# amplivias.net
KiCad netlist of a schematic drawn in EAGLE
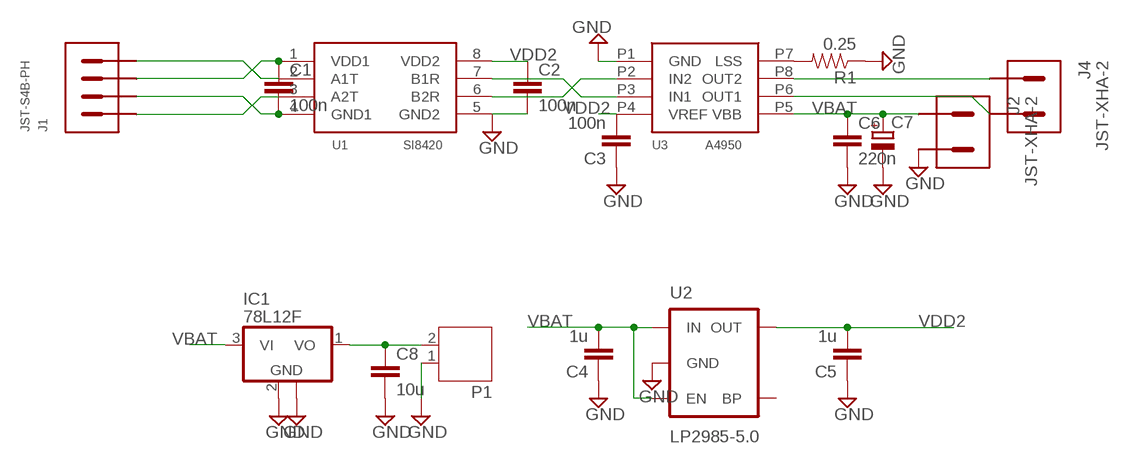
[diagram p0: schematic, sheet 1]

(export (version "E")
  (design (tool "Eeschema 10.0.6"))
  (components
    (comp (ref "C1")
      (value "100n")
      (footprint "eagle-import:0603-CAP")
      (libsource (lib "eagle-import") (part "CAP0603-CAP"))
    )
    (comp (ref "C2")
      (value "100n")
      (footprint "eagle-import:0603-CAP")
      (libsource (lib "eagle-import") (part "CAP0603-CAP"))
    )
    (comp (ref "C3")
      (value "100n")
      (footprint "eagle-import:0603-CAP")
      (libsource (lib "eagle-import") (part "CAP0603-CAP"))
    )
    (comp (ref "C4")
      (value "1u")
      (footprint "eagle-import:0603-CAP")
      (libsource (lib "eagle-import") (part "CAP0603-CAP"))
    )
    (comp (ref "C5")
      (value "1u")
      (footprint "eagle-import:0603-CAP")
      (libsource (lib "eagle-import") (part "CAP0603-CAP"))
    )
    (comp (ref "C6")
      (value "220n")
      (footprint "eagle-import:C0805")
      (libsource (lib "eagle-import") (part "C-EUC0805"))
    )
    (comp (ref "C7")
      (value "CPOL-EUSANYO_SMD_E7")
      (footprint "eagle-import:SANYO-OSCON_SMD_E7")
      (libsource (lib "eagle-import") (part "CPOL-EUSANYO_SMD_E7"))
    )
    (comp (ref "C8")
      (value "10u")
      (footprint "eagle-import:C0805")
      (libsource (lib "eagle-import") (part "C-EUC0805"))
    )
    (comp (ref "IC1")
      (value "78L12F")
      (footprint "eagle-import:SOT89")
      (libsource (lib "eagle-import") (part "78LF12"))
    )
    (comp (ref "J1")
      (value "JST-S4B-PH")
      (footprint "eagle-import:JST-S4B-PH")
      (libsource (lib "eagle-import") (part "JST-S4B-PH"))
    )
    (comp (ref "J2")
      (value "JST-XHA-2")
      (footprint "eagle-import:JST-XHA-2")
      (libsource (lib "eagle-import") (part "JST-XHA-2"))
    )
    (comp (ref "J4")
      (value "JST-XHA-2")
      (footprint "eagle-import:JST-XHA-2")
      (libsource (lib "eagle-import") (part "JST-XHA-2"))
    )
    (comp (ref "P1")
      (value "JST-PH2")
      (footprint "eagle-import:JST-PH2")
      (libsource (lib "eagle-import") (part "JST-PH2"))
    )
    (comp (ref "R1")
      (value "0.25")
      (footprint "eagle-import:R2512")
      (libsource (lib "eagle-import") (part "RESISTOR2512"))
    )
    (comp (ref "U1")
      (value "SI8420")
      (footprint "eagle-import:SO-08")
      (libsource (lib "eagle-import") (part "SI8420"))
    )
    (comp (ref "U2")
      (value "LP2985-5.0")
      (footprint "eagle-import:SOT23-5")
      (libsource (lib "eagle-import") (part "MIC52055V"))
    )
    (comp (ref "U3")
      (value "A4950")
      (footprint "eagle-import:SOIC8THROUG")
      (libsource (lib "eagle-import") (part "A4950"))
    )
  )
  (nets
    (net (code "1") (name "/VBAT") (class "Default")
      (node (ref "C4") (pin "2") (pinfunction "2_2") (pintype "passive"))
      (node (ref "C6") (pin "1") (pinfunction "1_1") (pintype "passive"))
      (node (ref "C7") (pin "+") (pinfunction "+_+") (pintype "passive"))
      (node (ref "IC1") (pin "3") (pinfunction "VI_3") (pintype "input"))
      (node (ref "J2") (pin "P$1") (pinfunction "P1_P$1") (pintype "bidirectional"))
      (node (ref "U2") (pin "1") (pinfunction "IN_1") (pintype "input"))
      (node (ref "U2") (pin "3") (pinfunction "EN_3") (pintype "input"))
      (node (ref "U3") (pin "P5") (pinfunction "VBB_P5") (pintype "bidirectional"))
    )
    (net (code "2") (name "/VDD2") (class "Default")
      (node (ref "C2") (pin "1") (pinfunction "1_1") (pintype "passive"))
      (node (ref "C3") (pin "2") (pinfunction "2_2") (pintype "passive"))
      (node (ref "C5") (pin "2") (pinfunction "2_2") (pintype "passive"))
      (node (ref "U1") (pin "8") (pinfunction "VDD2_8") (pintype "bidirectional"))
      (node (ref "U2") (pin "5") (pinfunction "OUT_5") (pintype "passive"))
      (node (ref "U3") (pin "P4") (pinfunction "VREF_P4") (pintype "bidirectional"))
    )
    (net (code "3") (name "GND") (class "Default")
      (node (ref "C2") (pin "2") (pinfunction "2_2") (pintype "passive"))
      (node (ref "C3") (pin "1") (pinfunction "1_1") (pintype "passive"))
      (node (ref "C4") (pin "1") (pinfunction "1_1") (pintype "passive"))
      (node (ref "C5") (pin "1") (pinfunction "1_1") (pintype "passive"))
      (node (ref "C6") (pin "2") (pinfunction "2_2") (pintype "passive"))
      (node (ref "C7") (pin "-") (pinfunction "-_-") (pintype "passive"))
      (node (ref "C8") (pin "2") (pinfunction "2_2") (pintype "passive"))
      (node (ref "IC1") (pin "2") (pinfunction "GND_2") (pintype "passive"))
      (node (ref "IC1") (pin "2@1") (pinfunction "GND_2@1") (pintype "passive"))
      (node (ref "J2") (pin "P$2") (pinfunction "P2_P$2") (pintype "bidirectional"))
      (node (ref "P1") (pin "1") (pinfunction "1_1") (pintype "passive"))
      (node (ref "R1") (pin "1") (pinfunction "1_1") (pintype "passive"))
      (node (ref "U1") (pin "5") (pinfunction "GND2_5") (pintype "bidirectional"))
      (node (ref "U2") (pin "2") (pinfunction "GND_2") (pintype "input"))
      (node (ref "U3") (pin "P1") (pinfunction "GND_P1") (pintype "bidirectional"))
    )
    (net (code "4") (name "Net-(IC1-VO)") (class "Default")
      (node (ref "C8") (pin "1") (pinfunction "1_1") (pintype "passive"))
      (node (ref "IC1") (pin "1") (pinfunction "VO_1") (pintype "passive"))
      (node (ref "P1") (pin "2") (pinfunction "2_2") (pintype "passive"))
    )
    (net (code "5") (name "Net-(J4-P1)") (class "Default")
      (node (ref "J4") (pin "P$1") (pinfunction "P1_P$1") (pintype "bidirectional"))
      (node (ref "U3") (pin "P8") (pinfunction "OUT2_P8") (pintype "bidirectional"))
    )
    (net (code "6") (name "Net-(J4-P2)") (class "Default")
      (node (ref "J4") (pin "P$2") (pinfunction "P2_P$2") (pintype "bidirectional"))
      (node (ref "U3") (pin "P6") (pinfunction "OUT1_P6") (pintype "bidirectional"))
    )
    (net (code "7") (name "Net-(U1-A1T)") (class "Default")
      (node (ref "J1") (pin "P$4") (pinfunction "P$4_P$4") (pintype "bidirectional"))
      (node (ref "U1") (pin "2") (pinfunction "A1T_2") (pintype "bidirectional"))
    )
    (net (code "8") (name "Net-(U1-A2T)") (class "Default")
      (node (ref "J1") (pin "P$1") (pinfunction "P$1_P$1") (pintype "bidirectional"))
      (node (ref "U1") (pin "3") (pinfunction "A2T_3") (pintype "bidirectional"))
    )
    (net (code "9") (name "Net-(U1-B1R)") (class "Default")
      (node (ref "U1") (pin "7") (pinfunction "B1R_7") (pintype "bidirectional"))
      (node (ref "U3") (pin "P3") (pinfunction "IN1_P3") (pintype "bidirectional"))
    )
    (net (code "10") (name "Net-(U1-B2R)") (class "Default")
      (node (ref "U1") (pin "6") (pinfunction "B2R_6") (pintype "bidirectional"))
      (node (ref "U3") (pin "P2") (pinfunction "IN2_P2") (pintype "bidirectional"))
    )
    (net (code "11") (name "Net-(U1-GND1)") (class "Default")
      (node (ref "C1") (pin "2") (pinfunction "2_2") (pintype "passive"))
      (node (ref "J1") (pin "P$2") (pinfunction "P$2_P$2") (pintype "bidirectional"))
      (node (ref "U1") (pin "4") (pinfunction "GND1_4") (pintype "bidirectional"))
    )
    (net (code "12") (name "Net-(U1-VDD1)") (class "Default")
      (node (ref "C1") (pin "1") (pinfunction "1_1") (pintype "passive"))
      (node (ref "J1") (pin "P$3") (pinfunction "P$3_P$3") (pintype "bidirectional"))
      (node (ref "U1") (pin "1") (pinfunction "VDD1_1") (pintype "bidirectional"))
    )
    (net (code "13") (name "Net-(U3-LSS)") (class "Default")
      (node (ref "R1") (pin "2") (pinfunction "2_2") (pintype "passive"))
      (node (ref "U3") (pin "P7") (pinfunction "LSS_P7") (pintype "bidirectional"))
    )
    (net (code "14") (name "unconnected-(U2-BP-Pad4)") (class "Default")
      (node (ref "U2") (pin "4") (pinfunction "BP_4") (pintype "input"))
    )
  )
)
